# PICTrack.net
KiCad netlist of a schematic drawn in EAGLE
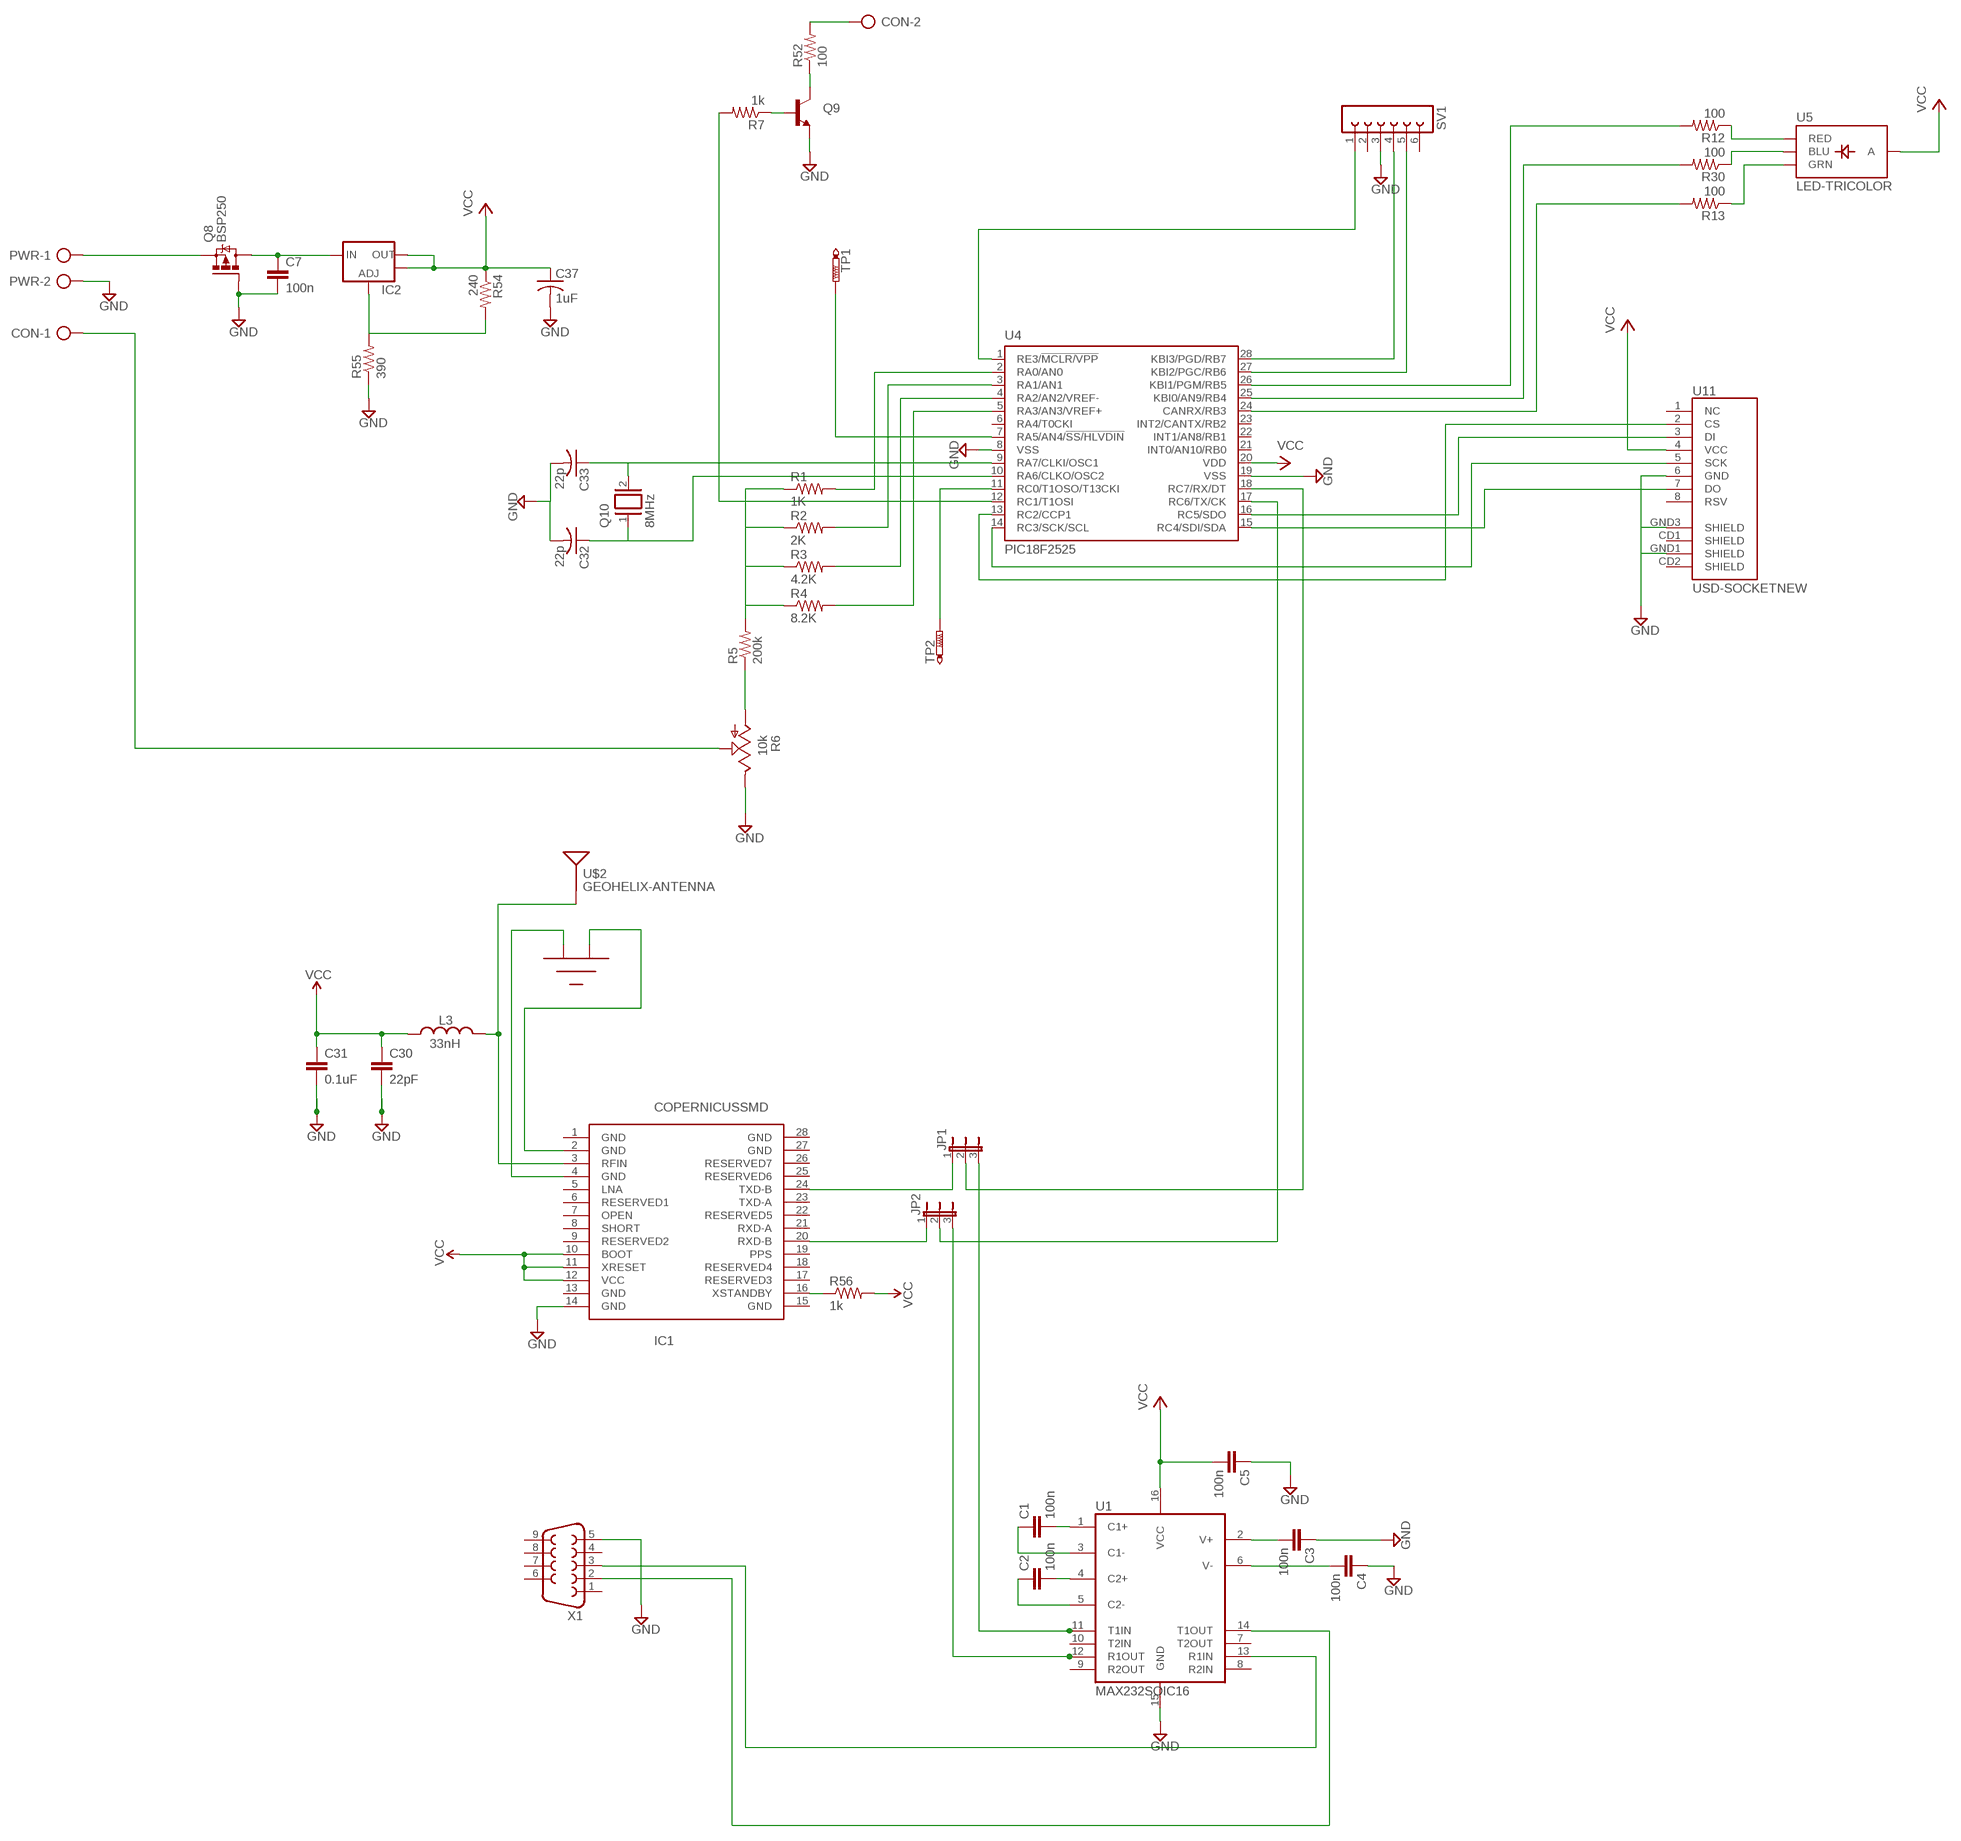
[diagram p0: schematic, sheet 1]

(export (version "E")
  (design (tool "Eeschema 10.0.6"))
  (components
    (comp (ref "C1")
      (value "100n")
      (footprint "eagle-import:C0402")
      (libsource (lib "eagle-import") (part "C-EUC0402"))
    )
    (comp (ref "C2")
      (value "100n")
      (footprint "eagle-import:C0402")
      (libsource (lib "eagle-import") (part "C-EUC0402"))
    )
    (comp (ref "C3")
      (value "100n")
      (footprint "eagle-import:C0402")
      (libsource (lib "eagle-import") (part "C-EUC0402"))
    )
    (comp (ref "C4")
      (value "100n")
      (footprint "eagle-import:C0402")
      (libsource (lib "eagle-import") (part "C-EUC0402"))
    )
    (comp (ref "C5")
      (value "100n")
      (footprint "eagle-import:C0402")
      (libsource (lib "eagle-import") (part "C-EUC0402"))
    )
    (comp (ref "C7")
      (value "100n")
      (footprint "eagle-import:C0402")
      (libsource (lib "eagle-import") (part "C-EUC0402"))
    )
    (comp (ref "C30")
      (value "22pF")
      (footprint "eagle-import:0402-CAP")
      (libsource (lib "eagle-import") (part "CAP0402-CAP"))
    )
    (comp (ref "C31")
      (value "0.1uF")
      (footprint "eagle-import:0402-CAP")
      (libsource (lib "eagle-import") (part "CAP0402-CAP"))
    )
    (comp (ref "C32")
      (value "22p")
      (footprint "eagle-import:C0603")
      (libsource (lib "eagle-import") (part "C-USC0603"))
    )
    (comp (ref "C33")
      (value "22p")
      (footprint "eagle-import:C0603")
      (libsource (lib "eagle-import") (part "C-USC0603"))
    )
    (comp (ref "C37")
      (value "1uF")
      (footprint "eagle-import:C025-030X050")
      (libsource (lib "eagle-import") (part "resistor_C-US025-030X050"))
    )
    (comp (ref "CON")
      (value "AK300/2")
      (footprint "eagle-import:AK300_2")
      (libsource (lib "eagle-import") (part "AK300/2"))
    )
    (comp (ref "IC1")
      (value "COPERNICUSSMD")
      (footprint "eagle-import:COPERNICUS")
      (libsource (lib "eagle-import") (part "COPERNICUSSMD"))
    )
    (comp (ref "IC2")
      (value "V_REG_LM1117SOT223")
      (footprint "eagle-import:SOT223")
      (libsource (lib "eagle-import") (part "V_REG_LM1117SOT223"))
    )
    (comp (ref "JP1")
      (value "JP2E")
      (footprint "eagle-import:JP2")
      (libsource (lib "eagle-import") (part "JP2E"))
    )
    (comp (ref "JP2")
      (value "JP2E")
      (footprint "eagle-import:JP2")
      (libsource (lib "eagle-import") (part "JP2E"))
    )
    (comp (ref "L3")
      (value "33nH")
      (footprint "eagle-import:C0402")
      (libsource (lib "eagle-import") (part "INDUCTOR0402"))
    )
    (comp (ref "PWR")
      (value "AK300/2")
      (footprint "eagle-import:AK300_2")
      (libsource (lib "eagle-import") (part "AK300/2"))
    )
    (comp (ref "Q8")
      (value "BSP250")
      (footprint "eagle-import:SOT223")
      (libsource (lib "eagle-import") (part "BSP250"))
    )
    (comp (ref "Q9")
      (value "TRANSISTOR_NPNSOT23")
      (footprint "eagle-import:SOT23")
      (libsource (lib "eagle-import") (part "TRANSISTOR_NPNSOT23"))
    )
    (comp (ref "Q10")
      (value "8MHz")
      (footprint "eagle-import:QS")
      (libsource (lib "eagle-import") (part "XTAL/S"))
    )
    (comp (ref "R1")
      (value "1K")
      (footprint "eagle-import:0411V")
      (libsource (lib "eagle-import") (part "R-US_0411/3V"))
    )
    (comp (ref "R2")
      (value "2K")
      (footprint "eagle-import:0411V")
      (libsource (lib "eagle-import") (part "R-US_0411/3V"))
    )
    (comp (ref "R3")
      (value "4.2K")
      (footprint "eagle-import:0411V")
      (libsource (lib "eagle-import") (part "R-US_0411/3V"))
    )
    (comp (ref "R4")
      (value "8.2K")
      (footprint "eagle-import:0411V")
      (libsource (lib "eagle-import") (part "R-US_0411/3V"))
    )
    (comp (ref "R5")
      (value "200k")
      (footprint "eagle-import:0411V")
      (libsource (lib "eagle-import") (part "R-US_0411/3V"))
    )
    (comp (ref "R6")
      (value "10k")
      (footprint "eagle-import:CA6V")
      (libsource (lib "eagle-import") (part "TRIM_US-CA6V"))
    )
    (comp (ref "R7")
      (value "1k")
      (footprint "eagle-import:R0603")
      (libsource (lib "eagle-import") (part "R-US_R0603"))
    )
    (comp (ref "R12")
      (value "100")
      (footprint "eagle-import:R0603")
      (libsource (lib "eagle-import") (part "R-US_R0603"))
    )
    (comp (ref "R13")
      (value "100")
      (footprint "eagle-import:R0603")
      (libsource (lib "eagle-import") (part "R-US_R0603"))
    )
    (comp (ref "R30")
      (value "100")
      (footprint "eagle-import:R0603")
      (libsource (lib "eagle-import") (part "R-US_R0603"))
    )
    (comp (ref "R52")
      (value "100")
      (footprint "eagle-import:0411V")
      (libsource (lib "eagle-import") (part "R-US_0411/3V"))
    )
    (comp (ref "R54")
      (value "240")
      (footprint "eagle-import:R0603")
      (libsource (lib "eagle-import") (part "R-US_R0603"))
    )
    (comp (ref "R55")
      (value "390")
      (footprint "eagle-import:R0603")
      (libsource (lib "eagle-import") (part "R-US_R0603"))
    )
    (comp (ref "R56")
      (value "1k")
      (footprint "eagle-import:R0603")
      (libsource (lib "eagle-import") (part "R-US_R0603"))
    )
    (comp (ref "SV1")
      (value "FE06-1")
      (footprint "eagle-import:FE06")
      (libsource (lib "eagle-import") (part "FE06-1"))
    )
    (comp (ref "TP1")
      (value "PTR1PAD1-13")
      (footprint "eagle-import:P1-13")
      (libsource (lib "eagle-import") (part "PTR1PAD1-13"))
    )
    (comp (ref "TP2")
      (value "PTR1PAD1-13")
      (footprint "eagle-import:P1-13")
      (libsource (lib "eagle-import") (part "PTR1PAD1-13"))
    )
    (comp (ref "U$2")
      (value "GEOHELIX-ANTENNA")
      (footprint "eagle-import:HELIXANTENNA")
      (libsource (lib "eagle-import") (part "GEOHELIX-ANTENNA"))
    )
    (comp (ref "U1")
      (value "MAX232SOIC16")
      (footprint "eagle-import:SO016")
      (libsource (lib "eagle-import") (part "MAX232SOIC16"))
    )
    (comp (ref "U4")
      (value "PIC18F2525")
      (footprint "eagle-import:SO28W")
      (libsource (lib "eagle-import") (part "PIC18F2525-SOIC"))
    )
    (comp (ref "U5")
      (value "LED-TRICOLOR")
      (footprint "eagle-import:LED-TRICOLOR-SMD")
      (libsource (lib "eagle-import") (part "LED-TRICOLOR"))
    )
    (comp (ref "U11")
      (value "USD-SOCKETNEW")
      (footprint "eagle-import:MICRO-SD-SOCKET-PP")
      (libsource (lib "eagle-import") (part "USD-SOCKETNEW"))
    )
    (comp (ref "X1")
      (value "DB9FEMALE")
      (footprint "eagle-import:DB9")
      (libsource (lib "eagle-import") (part "DB9FEMALE"))
    )
  )
  (nets
    (net (code "1") (name "GND") (class "Default")
      (node (ref "C3") (pin "1") (pinfunction "1_1") (pintype "passive"))
      (node (ref "C30") (pin "2") (pinfunction "2_2") (pintype "passive"))
      (node (ref "C31") (pin "2") (pinfunction "2_2") (pintype "passive"))
      (node (ref "C32") (pin "2") (pinfunction "2_2") (pintype "passive"))
      (node (ref "C33") (pin "2") (pinfunction "2_2") (pintype "passive"))
      (node (ref "C37") (pin "2") (pinfunction "2_2") (pintype "passive"))
      (node (ref "C4") (pin "1") (pinfunction "1_1") (pintype "passive"))
      (node (ref "C5") (pin "1") (pinfunction "1_1") (pintype "passive"))
      (node (ref "C7") (pin "2") (pinfunction "2_2") (pintype "passive"))
      (node (ref "IC1") (pin "14") (pinfunction "GND_14") (pintype "bidirectional"))
      (node (ref "PWR") (pin "2") (pinfunction "KL_2") (pintype "passive"))
      (node (ref "Q8") (pin "1") (pinfunction "G_1") (pintype "passive"))
      (node (ref "Q9") (pin "2") (pinfunction "E_2") (pintype "passive"))
      (node (ref "R55") (pin "1") (pinfunction "1_1") (pintype "passive"))
      (node (ref "R6") (pin "E") (pinfunction "E_E") (pintype "passive"))
      (node (ref "SV1") (pin "3") (pinfunction "3_3") (pintype "passive"))
      (node (ref "U1") (pin "15") (pinfunction "GND_15") (pintype "bidirectional"))
      (node (ref "U11") (pin "6") (pinfunction "GND_6") (pintype "bidirectional"))
      (node (ref "U11") (pin "GND1") (pinfunction "SHIELD_GND1") (pintype "bidirectional"))
      (node (ref "U11") (pin "GND3") (pinfunction "SHIELD_GND3") (pintype "bidirectional"))
      (node (ref "U4") (pin "19") (pinfunction "VSS_19") (pintype "power_in"))
      (node (ref "U4") (pin "8") (pinfunction "VSS_8") (pintype "power_in"))
      (node (ref "X1") (pin "5") (pinfunction "5_5") (pintype "passive"))
    )
    (net (code "2") (name "Net-(CONA-KL)") (class "Default")
      (node (ref "CON") (pin "1") (pinfunction "KL_1") (pintype "passive"))
      (node (ref "R6") (pin "S") (pinfunction "S_S") (pintype "passive"))
    )
    (net (code "3") (name "Net-(CONB-KL)") (class "Default")
      (node (ref "CON") (pin "2") (pinfunction "KL_2") (pintype "passive"))
      (node (ref "R52") (pin "2") (pinfunction "2_2") (pintype "passive"))
    )
    (net (code "4") (name "Net-(IC1-RFIN)") (class "Default")
      (node (ref "IC1") (pin "3") (pinfunction "RFIN_3") (pintype "bidirectional"))
      (node (ref "L3") (pin "2") (pinfunction "2_2") (pintype "passive"))
      (node (ref "U$2") (pin "P$2") (pinfunction "SIGNAL_P$2") (pintype "bidirectional"))
    )
    (net (code "5") (name "Net-(IC1-RXD-B)") (class "Default")
      (node (ref "IC1") (pin "20") (pinfunction "RXD-B_20") (pintype "bidirectional"))
      (node (ref "JP2") (pin "1") (pinfunction "1_1") (pintype "passive"))
    )
    (net (code "6") (name "Net-(IC1-TXD-B)") (class "Default")
      (node (ref "IC1") (pin "24") (pinfunction "TXD-B_24") (pintype "bidirectional"))
      (node (ref "JP1") (pin "1") (pinfunction "1_1") (pintype "passive"))
    )
    (net (code "7") (name "Net-(IC1-XSTANDBY)") (class "Default")
      (node (ref "IC1") (pin "16") (pinfunction "XSTANDBY_16") (pintype "bidirectional"))
      (node (ref "R56") (pin "1") (pinfunction "1_1") (pintype "passive"))
    )
    (net (code "8") (name "Net-(IC2-ADJ)") (class "Default")
      (node (ref "IC2") (pin "1") (pinfunction "ADJ_1") (pintype "input"))
      (node (ref "R54") (pin "2") (pinfunction "2_2") (pintype "passive"))
      (node (ref "R55") (pin "2") (pinfunction "2_2") (pintype "passive"))
    )
    (net (code "9") (name "Net-(IC2-IN)") (class "Default")
      (node (ref "C7") (pin "1") (pinfunction "1_1") (pintype "passive"))
      (node (ref "IC2") (pin "3") (pinfunction "IN_3") (pintype "input"))
      (node (ref "Q8") (pin "2") (pinfunction "D_2") (pintype "passive"))
    )
    (net (code "10") (name "Net-(PWRA-KL)") (class "Default")
      (node (ref "PWR") (pin "1") (pinfunction "KL_1") (pintype "passive"))
      (node (ref "Q8") (pin "3") (pinfunction "S_3") (pintype "passive"))
    )
    (net (code "11") (name "Net-(Q9-B)") (class "Default")
      (node (ref "Q9") (pin "1") (pinfunction "B_1") (pintype "passive"))
      (node (ref "R7") (pin "1") (pinfunction "1_1") (pintype "passive"))
    )
    (net (code "12") (name "Net-(Q9-C)") (class "Default")
      (node (ref "Q9") (pin "3") (pinfunction "C_3") (pintype "passive"))
      (node (ref "R52") (pin "1") (pinfunction "1_1") (pintype "passive"))
    )
    (net (code "13") (name "Net-(R1-Pad1)") (class "Default")
      (node (ref "R1") (pin "1") (pinfunction "1_1") (pintype "passive"))
      (node (ref "R2") (pin "1") (pinfunction "1_1") (pintype "passive"))
      (node (ref "R3") (pin "1") (pinfunction "1_1") (pintype "passive"))
      (node (ref "R4") (pin "1") (pinfunction "1_1") (pintype "passive"))
      (node (ref "R5") (pin "2") (pinfunction "2_2") (pintype "passive"))
    )
    (net (code "14") (name "Net-(R5-Pad1)") (class "Default")
      (node (ref "R5") (pin "1") (pinfunction "1_1") (pintype "passive"))
      (node (ref "R6") (pin "A") (pinfunction "A_A") (pintype "passive"))
    )
    (net (code "15") (name "Net-(U$2-GND)") (class "Default")
      (node (ref "IC1") (pin "4") (pinfunction "GND_4") (pintype "bidirectional"))
      (node (ref "U$2") (pin "P$1") (pinfunction "GND_P$1") (pintype "bidirectional"))
    )
    (net (code "16") (name "Net-(U$2-GND1)") (class "Default")
      (node (ref "IC1") (pin "2") (pinfunction "GND_2") (pintype "bidirectional"))
      (node (ref "U$2") (pin "P$3") (pinfunction "GND1_P$3") (pintype "bidirectional"))
    )
    (net (code "17") (name "Net-(U1-C1+)") (class "Default")
      (node (ref "C1") (pin "2") (pinfunction "2_2") (pintype "passive"))
      (node (ref "U1") (pin "1") (pinfunction "C1+_1") (pintype "bidirectional"))
    )
    (net (code "18") (name "Net-(U1-C1-)") (class "Default")
      (node (ref "C1") (pin "1") (pinfunction "1_1") (pintype "passive"))
      (node (ref "U1") (pin "3") (pinfunction "C1-_3") (pintype "bidirectional"))
    )
    (net (code "19") (name "Net-(U1-C2+)") (class "Default")
      (node (ref "C2") (pin "2") (pinfunction "2_2") (pintype "passive"))
      (node (ref "U1") (pin "4") (pinfunction "C2+_4") (pintype "bidirectional"))
    )
    (net (code "20") (name "Net-(U1-C2-)") (class "Default")
      (node (ref "C2") (pin "1") (pinfunction "1_1") (pintype "passive"))
      (node (ref "U1") (pin "5") (pinfunction "C2-_5") (pintype "bidirectional"))
    )
    (net (code "21") (name "Net-(U1-R1IN)") (class "Default")
      (node (ref "U1") (pin "13") (pinfunction "R1IN_13") (pintype "input"))
      (node (ref "X1") (pin "3") (pinfunction "3_3") (pintype "passive"))
    )
    (net (code "22") (name "Net-(U1-R1OUT)") (class "Default")
      (node (ref "JP2") (pin "3") (pinfunction "3_3") (pintype "passive"))
      (node (ref "U1") (pin "12") (pinfunction "R1OUT_12") (pintype "output"))
    )
    (net (code "23") (name "Net-(U1-T1IN)") (class "Default")
      (node (ref "JP1") (pin "3") (pinfunction "3_3") (pintype "passive"))
      (node (ref "U1") (pin "11") (pinfunction "T1IN_11") (pintype "input"))
    )
    (net (code "24") (name "Net-(U1-T1OUT)") (class "Default")
      (node (ref "U1") (pin "14") (pinfunction "T1OUT_14") (pintype "output"))
      (node (ref "X1") (pin "2") (pinfunction "2_2") (pintype "passive"))
    )
    (net (code "25") (name "Net-(U1-V+)") (class "Default")
      (node (ref "C3") (pin "2") (pinfunction "2_2") (pintype "passive"))
      (node (ref "U1") (pin "2") (pinfunction "V+_2") (pintype "bidirectional"))
    )
    (net (code "26") (name "Net-(U1-V-)") (class "Default")
      (node (ref "C4") (pin "2") (pinfunction "2_2") (pintype "passive"))
      (node (ref "U1") (pin "6") (pinfunction "V-_6") (pintype "bidirectional"))
    )
    (net (code "27") (name "Net-(U4-CANRX{slash}RB3)") (class "Default")
      (node (ref "R13") (pin "2") (pinfunction "2_2") (pintype "passive"))
      (node (ref "U4") (pin "24") (pinfunction "CANRX/RB3_24") (pintype "bidirectional"))
    )
    (net (code "28") (name "Net-(U4-KBI0{slash}AN9{slash}RB4)") (class "Default")
      (node (ref "R30") (pin "2") (pinfunction "2_2") (pintype "passive"))
      (node (ref "U4") (pin "25") (pinfunction "KBI0/AN9/RB4_25") (pintype "bidirectional"))
    )
    (net (code "29") (name "Net-(U4-KBI1{slash}PGM{slash}RB5)") (class "Default")
      (node (ref "R12") (pin "2") (pinfunction "2_2") (pintype "passive"))
      (node (ref "U4") (pin "26") (pinfunction "KBI1/PGM/RB5_26") (pintype "bidirectional"))
    )
    (net (code "30") (name "Net-(U4-KBI2{slash}PGC{slash}RB6)") (class "Default")
      (node (ref "SV1") (pin "5") (pinfunction "5_5") (pintype "passive"))
      (node (ref "U4") (pin "27") (pinfunction "KBI2/PGC/RB6_27") (pintype "bidirectional"))
    )
    (net (code "31") (name "Net-(U4-KBI3{slash}PGD{slash}RB7)") (class "Default")
      (node (ref "SV1") (pin "4") (pinfunction "4_4") (pintype "passive"))
      (node (ref "U4") (pin "28") (pinfunction "KBI3/PGD/RB7_28") (pintype "bidirectional"))
    )
    (net (code "32") (name "Net-(U4-RA0{slash}AN0)") (class "Default")
      (node (ref "R1") (pin "2") (pinfunction "2_2") (pintype "passive"))
      (node (ref "U4") (pin "2") (pinfunction "RA0/AN0_2") (pintype "bidirectional"))
    )
    (net (code "33") (name "Net-(U4-RA1{slash}AN1)") (class "Default")
      (node (ref "R2") (pin "2") (pinfunction "2_2") (pintype "passive"))
      (node (ref "U4") (pin "3") (pinfunction "RA1/AN1_3") (pintype "bidirectional"))
    )
    (net (code "34") (name "Net-(U4-RA2{slash}AN2{slash}VREF-)") (class "Default")
      (node (ref "R3") (pin "2") (pinfunction "2_2") (pintype "passive"))
      (node (ref "U4") (pin "4") (pinfunction "RA2/AN2/VREF-_4") (pintype "bidirectional"))
    )
    (net (code "35") (name "Net-(U4-RA3{slash}AN3{slash}VREF+)") (class "Default")
      (node (ref "R4") (pin "2") (pinfunction "2_2") (pintype "passive"))
      (node (ref "U4") (pin "5") (pinfunction "RA3/AN3/VREF+_5") (pintype "bidirectional"))
    )
    (net (code "36") (name "Net-(U4-RA5{slash}AN4{slash}~{SS{slash}HLVDIN})") (class "Default")
      (node (ref "TP1") (pin "TP") (pinfunction "TP_TP") (pintype "input"))
      (node (ref "U4") (pin "7") (pinfunction "RA5/AN4/~{SS/HLVDIN}_7") (pintype "bidirectional"))
    )
    (net (code "37") (name "Net-(U4-RA6{slash}CLKO{slash}OSC2)") (class "Default")
      (node (ref "C32") (pin "1") (pinfunction "1_1") (pintype "passive"))
      (node (ref "Q10") (pin "1") (pinfunction "1_1") (pintype "passive"))
      (node (ref "U4") (pin "10") (pinfunction "RA6/CLKO/OSC2_10") (pintype "output"))
    )
    (net (code "38") (name "Net-(U4-RA7{slash}CLKI{slash}OSC1)") (class "Default")
      (node (ref "C33") (pin "1") (pinfunction "1_1") (pintype "passive"))
      (node (ref "Q10") (pin "2") (pinfunction "2_2") (pintype "passive"))
      (node (ref "U4") (pin "9") (pinfunction "RA7/CLKI/OSC1_9") (pintype "input"))
    )
    (net (code "39") (name "Net-(U4-RC0{slash}T1OSO{slash}T13CKI)") (class "Default")
      (node (ref "TP2") (pin "TP") (pinfunction "TP_TP") (pintype "input"))
      (node (ref "U4") (pin "11") (pinfunction "RC0/T1OSO/T13CKI_11") (pintype "bidirectional"))
    )
    (net (code "40") (name "Net-(U4-RC1{slash}T1OSI)") (class "Default")
      (node (ref "R7") (pin "2") (pinfunction "2_2") (pintype "passive"))
      (node (ref "U4") (pin "12") (pinfunction "RC1/T1OSI_12") (pintype "bidirectional"))
    )
    (net (code "41") (name "Net-(U4-RC6{slash}TX{slash}CK)") (class "Default")
      (node (ref "JP2") (pin "2") (pinfunction "2_2") (pintype "passive"))
      (node (ref "U4") (pin "17") (pinfunction "RC6/TX/CK_17") (pintype "bidirectional"))
    )
    (net (code "42") (name "Net-(U4-RC7{slash}RX{slash}DT)") (class "Default")
      (node (ref "JP1") (pin "2") (pinfunction "2_2") (pintype "passive"))
      (node (ref "U4") (pin "18") (pinfunction "RC7/RX/DT_18") (pintype "bidirectional"))
    )
    (net (code "43") (name "Net-(U4-RE3{slash}~{MCLR{slash}VPP})") (class "Default")
      (node (ref "SV1") (pin "1") (pinfunction "1_1") (pintype "passive"))
      (node (ref "U4") (pin "1") (pinfunction "RE3/~{MCLR/VPP}_1") (pintype "input"))
    )
    (net (code "44") (name "Net-(U5-BLU)") (class "Default")
      (node (ref "R30") (pin "1") (pinfunction "1_1") (pintype "passive"))
      (node (ref "U5") (pin "B") (pinfunction "BLU_B") (pintype "bidirectional"))
    )
    (net (code "45") (name "Net-(U5-GRN)") (class "Default")
      (node (ref "R13") (pin "1") (pinfunction "1_1") (pintype "passive"))
      (node (ref "U5") (pin "G") (pinfunction "GRN_G") (pintype "bidirectional"))
    )
    (net (code "46") (name "Net-(U5-RED)") (class "Default")
      (node (ref "R12") (pin "1") (pinfunction "1_1") (pintype "passive"))
      (node (ref "U5") (pin "R") (pinfunction "RED_R") (pintype "bidirectional"))
    )
    (net (code "47") (name "Net-(U11-CS)") (class "Default")
      (node (ref "U11") (pin "2") (pinfunction "CS_2") (pintype "bidirectional"))
      (node (ref "U4") (pin "13") (pinfunction "RC2/CCP1_13") (pintype "bidirectional"))
    )
    (net (code "48") (name "Net-(U11-DI)") (class "Default")
      (node (ref "U11") (pin "3") (pinfunction "DI_3") (pintype "bidirectional"))
      (node (ref "U4") (pin "16") (pinfunction "RC5/SDO_16") (pintype "bidirectional"))
    )
    (net (code "49") (name "Net-(U11-DO)") (class "Default")
      (node (ref "U11") (pin "7") (pinfunction "DO_7") (pintype "bidirectional"))
      (node (ref "U4") (pin "15") (pinfunction "RC4/SDI/SDA_15") (pintype "bidirectional"))
    )
    (net (code "50") (name "Net-(U11-SCK)") (class "Default")
      (node (ref "U11") (pin "5") (pinfunction "SCK_5") (pintype "bidirectional"))
      (node (ref "U4") (pin "14") (pinfunction "RC3/SCK/SCL_14") (pintype "bidirectional"))
    )
    (net (code "51") (name "VCC") (class "Default")
      (node (ref "C30") (pin "1") (pinfunction "1_1") (pintype "passive"))
      (node (ref "C31") (pin "1") (pinfunction "1_1") (pintype "passive"))
      (node (ref "C37") (pin "1") (pinfunction "1_1") (pintype "passive"))
      (node (ref "C5") (pin "2") (pinfunction "2_2") (pintype "passive"))
      (node (ref "IC1") (pin "10") (pinfunction "BOOT_10") (pintype "bidirectional"))
      (node (ref "IC1") (pin "11") (pinfunction "XRESET_11") (pintype "bidirectional"))
      (node (ref "IC1") (pin "12") (pinfunction "VCC_12") (pintype "bidirectional"))
      (node (ref "IC2") (pin "2") (pinfunction "OUT_2") (pintype "output"))
      (node (ref "IC2") (pin "4") (pinfunction "OUT_4") (pintype "output"))
      (node (ref "L3") (pin "1") (pinfunction "1_1") (pintype "passive"))
      (node (ref "R54") (pin "1") (pinfunction "1_1") (pintype "passive"))
      (node (ref "R56") (pin "2") (pinfunction "2_2") (pintype "passive"))
      (node (ref "U1") (pin "16") (pinfunction "VCC_16") (pintype "bidirectional"))
      (node (ref "U11") (pin "4") (pinfunction "VCC_4") (pintype "bidirectional"))
      (node (ref "U4") (pin "20") (pinfunction "VDD_20") (pintype "power_in"))
      (node (ref "U5") (pin "A") (pinfunction "A_A") (pintype "bidirectional"))
    )
    (net (code "52") (name "unconnected-(IC1-GND-Pad1)") (class "Default")
      (node (ref "IC1") (pin "1") (pinfunction "GND_1") (pintype "bidirectional"))
    )
    (net (code "53") (name "unconnected-(IC1-GND-Pad13)") (class "Default")
      (node (ref "IC1") (pin "13") (pinfunction "GND_13") (pintype "bidirectional"))
    )
    (net (code "54") (name "unconnected-(IC1-GND-Pad15)") (class "Default")
      (node (ref "IC1") (pin "15") (pinfunction "GND_15") (pintype "bidirectional"))
    )
    (net (code "55") (name "unconnected-(IC1-GND-Pad27)") (class "Default")
      (node (ref "IC1") (pin "27") (pinfunction "GND_27") (pintype "bidirectional"))
    )
    (net (code "56") (name "unconnected-(IC1-GND-Pad28)") (class "Default")
      (node (ref "IC1") (pin "28") (pinfunction "GND_28") (pintype "bidirectional"))
    )
    (net (code "57") (name "unconnected-(IC1-LNA-Pad5)") (class "Default")
      (node (ref "IC1") (pin "5") (pinfunction "LNA_5") (pintype "bidirectional"))
    )
    (net (code "58") (name "unconnected-(IC1-OPEN-Pad7)") (class "Default")
      (node (ref "IC1") (pin "7") (pinfunction "OPEN_7") (pintype "bidirectional"))
    )
    (net (code "59") (name "unconnected-(IC1-PPS-Pad19)") (class "Default")
      (node (ref "IC1") (pin "19") (pinfunction "PPS_19") (pintype "bidirectional"))
    )
    (net (code "60") (name "unconnected-(IC1-RESERVED1-Pad6)") (class "Default")
      (node (ref "IC1") (pin "6") (pinfunction "RESERVED1_6") (pintype "bidirectional"))
    )
    (net (code "61") (name "unconnected-(IC1-RESERVED2-Pad9)") (class "Default")
      (node (ref "IC1") (pin "9") (pinfunction "RESERVED2_9") (pintype "bidirectional"))
    )
    (net (code "62") (name "unconnected-(IC1-RESERVED3-Pad17)") (class "Default")
      (node (ref "IC1") (pin "17") (pinfunction "RESERVED3_17") (pintype "bidirectional"))
    )
    (net (code "63") (name "unconnected-(IC1-RESERVED4-Pad18)") (class "Default")
      (node (ref "IC1") (pin "18") (pinfunction "RESERVED4_18") (pintype "bidirectional"))
    )
    (net (code "64") (name "unconnected-(IC1-RESERVED5-Pad22)") (class "Default")
      (node (ref "IC1") (pin "22") (pinfunction "RESERVED5_22") (pintype "bidirectional"))
    )
    (net (code "65") (name "unconnected-(IC1-RESERVED6-Pad25)") (class "Default")
      (node (ref "IC1") (pin "25") (pinfunction "RESERVED6_25") (pintype "bidirectional"))
    )
    (net (code "66") (name "unconnected-(IC1-RESERVED7-Pad26)") (class "Default")
      (node (ref "IC1") (pin "26") (pinfunction "RESERVED7_26") (pintype "bidirectional"))
    )
    (net (code "67") (name "unconnected-(IC1-RXD-A-Pad21)") (class "Default")
      (node (ref "IC1") (pin "21") (pinfunction "RXD-A_21") (pintype "bidirectional"))
    )
    (net (code "68") (name "unconnected-(IC1-SHORT-Pad8)") (class "Default")
      (node (ref "IC1") (pin "8") (pinfunction "SHORT_8") (pintype "bidirectional"))
    )
    (net (code "69") (name "unconnected-(IC1-TXD-A-Pad23)") (class "Default")
      (node (ref "IC1") (pin "23") (pinfunction "TXD-A_23") (pintype "bidirectional"))
    )
    (net (code "70") (name "unconnected-(SV1-Pad2)") (class "Default")
      (node (ref "SV1") (pin "2") (pinfunction "2_2") (pintype "passive"))
    )
    (net (code "71") (name "unconnected-(SV1-Pad6)") (class "Default")
      (node (ref "SV1") (pin "6") (pinfunction "6_6") (pintype "passive"))
    )
    (net (code "72") (name "unconnected-(U1-R2IN-Pad8)") (class "Default")
      (node (ref "U1") (pin "8") (pinfunction "R2IN_8") (pintype "input"))
    )
    (net (code "73") (name "unconnected-(U1-R2OUT-Pad9)") (class "Default")
      (node (ref "U1") (pin "9") (pinfunction "R2OUT_9") (pintype "output"))
    )
    (net (code "74") (name "unconnected-(U1-T2IN-Pad10)") (class "Default")
      (node (ref "U1") (pin "10") (pinfunction "T2IN_10") (pintype "input"))
    )
    (net (code "75") (name "unconnected-(U1-T2OUT-Pad7)") (class "Default")
      (node (ref "U1") (pin "7") (pinfunction "T2OUT_7") (pintype "output"))
    )
    (net (code "76") (name "unconnected-(U4-INT0{slash}AN10{slash}RB0-Pad21)") (class "Default")
      (node (ref "U4") (pin "21") (pinfunction "INT0/AN10/RB0_21") (pintype "bidirectional"))
    )
    (net (code "77") (name "unconnected-(U4-INT1{slash}AN8{slash}RB1-Pad22)") (class "Default")
      (node (ref "U4") (pin "22") (pinfunction "INT1/AN8/RB1_22") (pintype "bidirectional"))
    )
    (net (code "78") (name "unconnected-(U4-INT2{slash}CANTX{slash}RB2-Pad23)") (class "Default")
      (node (ref "U4") (pin "23") (pinfunction "INT2/CANTX/RB2_23") (pintype "bidirectional"))
    )
    (net (code "79") (name "unconnected-(U4-RA4{slash}T0CKI-Pad6)") (class "Default")
      (node (ref "U4") (pin "6") (pinfunction "RA4/T0CKI_6") (pintype "bidirectional"))
    )
    (net (code "80") (name "unconnected-(U11-NC-Pad1)") (class "Default")
      (node (ref "U11") (pin "1") (pinfunction "NC_1") (pintype "bidirectional"))
    )
    (net (code "81") (name "unconnected-(U11-RSV-Pad8)") (class "Default")
      (node (ref "U11") (pin "8") (pinfunction "RSV_8") (pintype "bidirectional"))
    )
    (net (code "82") (name "unconnected-(U11-SHIELD-PadCD1)") (class "Default")
      (node (ref "U11") (pin "CD1") (pinfunction "SHIELD_CD1") (pintype "bidirectional"))
    )
    (net (code "83") (name "unconnected-(U11-SHIELD-PadCD2)") (class "Default")
      (node (ref "U11") (pin "CD2") (pinfunction "SHIELD_CD2") (pintype "bidirectional"))
    )
    (net (code "84") (name "unconnected-(X1-Pad1)") (class "Default")
      (node (ref "X1") (pin "1") (pinfunction "1_1") (pintype "passive"))
    )
    (net (code "85") (name "unconnected-(X1-Pad4)") (class "Default")
      (node (ref "X1") (pin "4") (pinfunction "4_4") (pintype "passive"))
    )
    (net (code "86") (name "unconnected-(X1-Pad6)") (class "Default")
      (node (ref "X1") (pin "6") (pinfunction "6_6") (pintype "passive"))
    )
    (net (code "87") (name "unconnected-(X1-Pad7)") (class "Default")
      (node (ref "X1") (pin "7") (pinfunction "7_7") (pintype "passive"))
    )
    (net (code "88") (name "unconnected-(X1-Pad8)") (class "Default")
      (node (ref "X1") (pin "8") (pinfunction "8_8") (pintype "passive"))
    )
    (net (code "89") (name "unconnected-(X1-Pad9)") (class "Default")
      (node (ref "X1") (pin "9") (pinfunction "9_9") (pintype "passive"))
    )
  )
)
